# FunctionGen.net
KiCad netlist of a schematic drawn in EAGLE
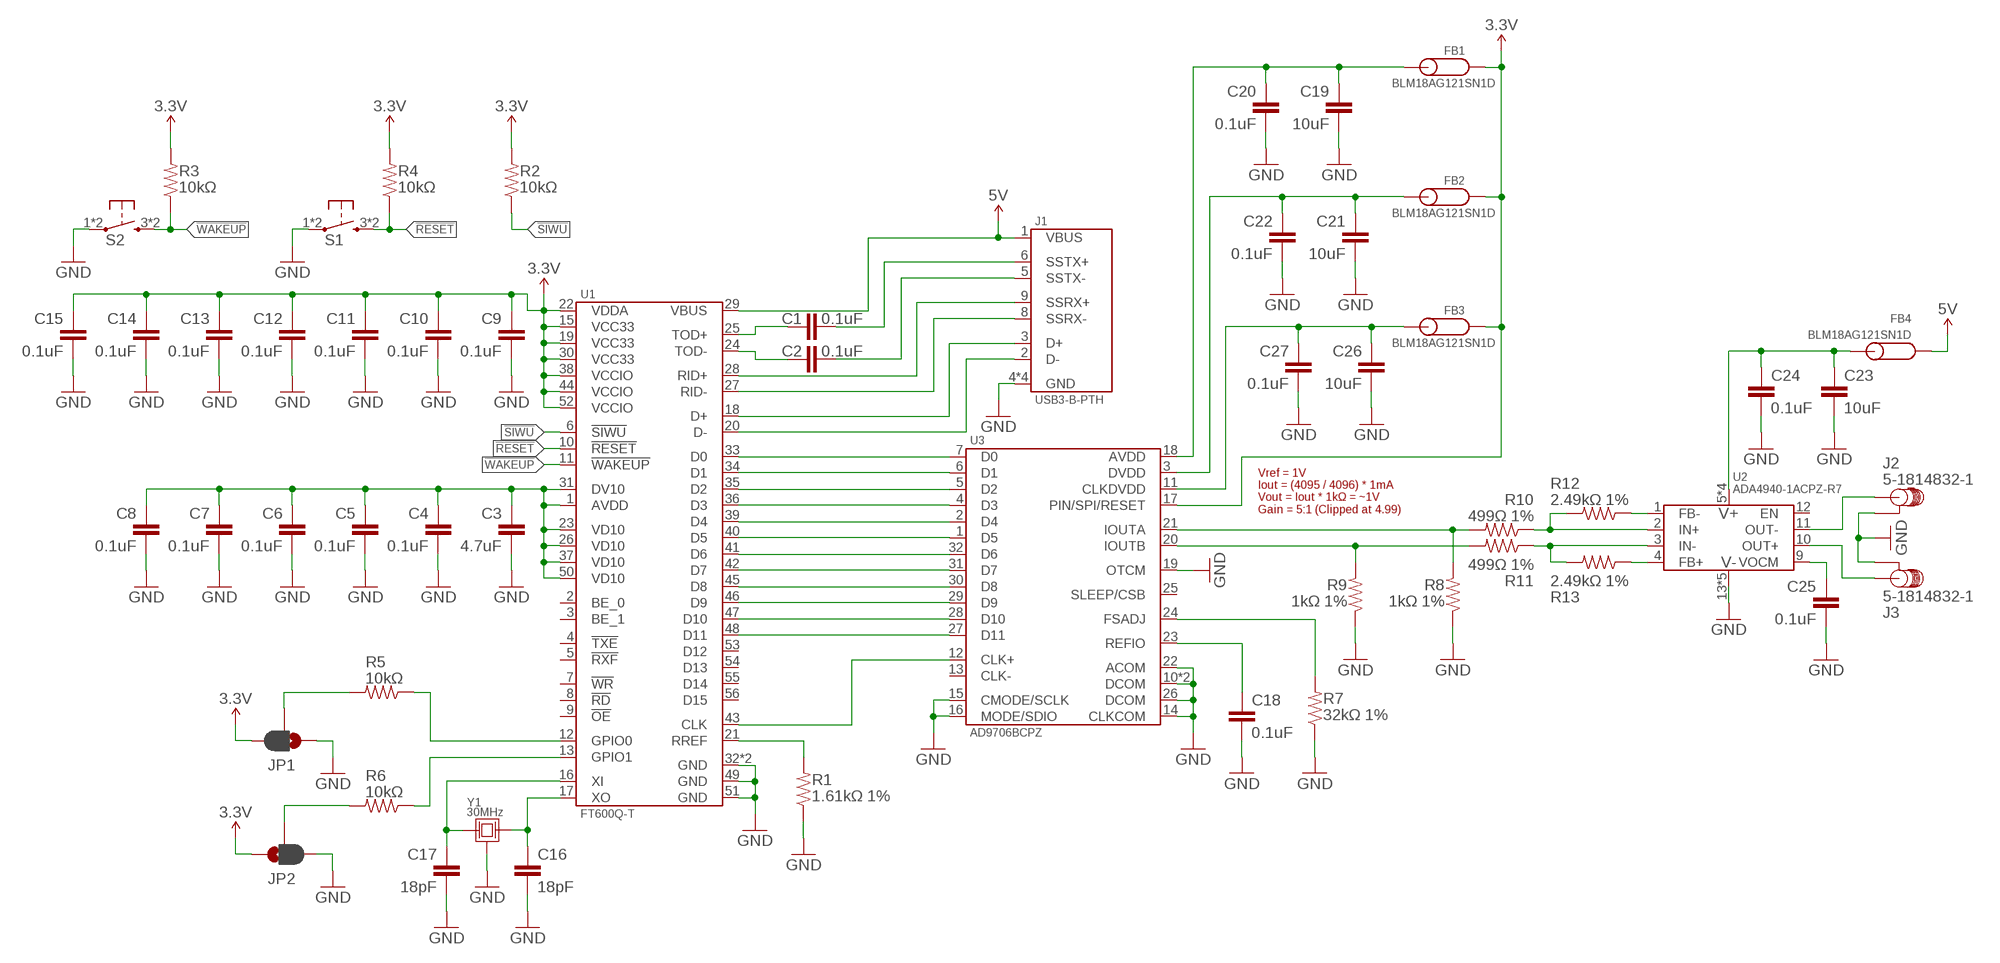
[diagram p0: schematic, sheet 1]

(export (version "E")
  (design (tool "Eeschema 10.0.6"))
  (components
    (comp (ref "C1")
      (value "0.1uF")
      (footprint "eagle-import:0603-CAP")
      (libsource (lib "eagle-import") (part "CAP-0603"))
    )
    (comp (ref "C2")
      (value "0.1uF")
      (footprint "eagle-import:0603-CAP")
      (libsource (lib "eagle-import") (part "CAP-0603"))
    )
    (comp (ref "C3")
      (value "4.7uF")
      (footprint "eagle-import:0603-CAP")
      (libsource (lib "eagle-import") (part "CAP-0603"))
    )
    (comp (ref "C4")
      (value "0.1uF")
      (footprint "eagle-import:0603-CAP")
      (libsource (lib "eagle-import") (part "CAP-0603"))
    )
    (comp (ref "C5")
      (value "0.1uF")
      (footprint "eagle-import:0603-CAP")
      (libsource (lib "eagle-import") (part "CAP-0603"))
    )
    (comp (ref "C6")
      (value "0.1uF")
      (footprint "eagle-import:0603-CAP")
      (libsource (lib "eagle-import") (part "CAP-0603"))
    )
    (comp (ref "C7")
      (value "0.1uF")
      (footprint "eagle-import:0603-CAP")
      (libsource (lib "eagle-import") (part "CAP-0603"))
    )
    (comp (ref "C8")
      (value "0.1uF")
      (footprint "eagle-import:0603-CAP")
      (libsource (lib "eagle-import") (part "CAP-0603"))
    )
    (comp (ref "C9")
      (value "0.1uF")
      (footprint "eagle-import:0603-CAP")
      (libsource (lib "eagle-import") (part "CAP-0603"))
    )
    (comp (ref "C10")
      (value "0.1uF")
      (footprint "eagle-import:0603-CAP")
      (libsource (lib "eagle-import") (part "CAP-0603"))
    )
    (comp (ref "C11")
      (value "0.1uF")
      (footprint "eagle-import:0603-CAP")
      (libsource (lib "eagle-import") (part "CAP-0603"))
    )
    (comp (ref "C12")
      (value "0.1uF")
      (footprint "eagle-import:0603-CAP")
      (libsource (lib "eagle-import") (part "CAP-0603"))
    )
    (comp (ref "C13")
      (value "0.1uF")
      (footprint "eagle-import:0603-CAP")
      (libsource (lib "eagle-import") (part "CAP-0603"))
    )
    (comp (ref "C14")
      (value "0.1uF")
      (footprint "eagle-import:0603-CAP")
      (libsource (lib "eagle-import") (part "CAP-0603"))
    )
    (comp (ref "C15")
      (value "0.1uF")
      (footprint "eagle-import:0603-CAP")
      (libsource (lib "eagle-import") (part "CAP-0603"))
    )
    (comp (ref "C16")
      (value "18pF")
      (footprint "eagle-import:0603-CAP")
      (libsource (lib "eagle-import") (part "CAP-0603"))
    )
    (comp (ref "C17")
      (value "18pF")
      (footprint "eagle-import:0603-CAP")
      (libsource (lib "eagle-import") (part "CAP-0603"))
    )
    (comp (ref "C18")
      (value "0.1uF")
      (footprint "eagle-import:0603-CAP")
      (libsource (lib "eagle-import") (part "CAP-0603"))
    )
    (comp (ref "C19")
      (value "10uF")
      (footprint "eagle-import:0603-CAP")
      (libsource (lib "eagle-import") (part "CAP-0603"))
    )
    (comp (ref "C20")
      (value "0.1uF")
      (footprint "eagle-import:0603-CAP")
      (libsource (lib "eagle-import") (part "CAP-0603"))
    )
    (comp (ref "C21")
      (value "10uF")
      (footprint "eagle-import:0603-CAP")
      (libsource (lib "eagle-import") (part "CAP-0603"))
    )
    (comp (ref "C22")
      (value "0.1uF")
      (footprint "eagle-import:0603-CAP")
      (libsource (lib "eagle-import") (part "CAP-0603"))
    )
    (comp (ref "C23")
      (value "10uF")
      (footprint "eagle-import:0603-CAP")
      (libsource (lib "eagle-import") (part "CAP-0603"))
    )
    (comp (ref "C24")
      (value "0.1uF")
      (footprint "eagle-import:0603-CAP")
      (libsource (lib "eagle-import") (part "CAP-0603"))
    )
    (comp (ref "C25")
      (value "0.1uF")
      (footprint "eagle-import:0603-CAP")
      (libsource (lib "eagle-import") (part "CAP-0603"))
    )
    (comp (ref "C26")
      (value "10uF")
      (footprint "eagle-import:0603-CAP")
      (libsource (lib "eagle-import") (part "CAP-0603"))
    )
    (comp (ref "C27")
      (value "0.1uF")
      (footprint "eagle-import:0603-CAP")
      (libsource (lib "eagle-import") (part "CAP-0603"))
    )
    (comp (ref "FB1")
      (value "BLM18AG121SN1D")
      (footprint "eagle-import:0603-FERRITE")
      (libsource (lib "eagle-import") (part "FERRITE-0603"))
    )
    (comp (ref "FB2")
      (value "BLM18AG121SN1D")
      (footprint "eagle-import:0603-FERRITE")
      (libsource (lib "eagle-import") (part "FERRITE-0603"))
    )
    (comp (ref "FB3")
      (value "BLM18AG121SN1D")
      (footprint "eagle-import:0603-FERRITE")
      (libsource (lib "eagle-import") (part "FERRITE-0603"))
    )
    (comp (ref "FB4")
      (value "BLM18AG121SN1D")
      (footprint "eagle-import:0603-FERRITE")
      (libsource (lib "eagle-import") (part "FERRITE-0603"))
    )
    (comp (ref "J1")
      (value "USB3-B-PTH")
      (footprint "eagle-import:GSB4211311WEU")
      (libsource (lib "eagle-import") (part "USB3-B-PTH"))
    )
    (comp (ref "J2")
      (value "5-1814832-1")
      (footprint "eagle-import:SMA-PTH")
      (libsource (lib "eagle-import") (part "SMA-PTH"))
    )
    (comp (ref "J3")
      (value "5-1814832-1")
      (footprint "eagle-import:SMA-PTH")
      (libsource (lib "eagle-import") (part "SMA-PTH"))
    )
    (comp (ref "JP1")
      (value "JUMPER-PAD-3-2OF3_NC_BY_PASTE")
      (footprint "eagle-import:PAD-JUMPER-3-2OF3_NC_BY_PASTE_YES_SILK_FULL_BOX")
      (libsource (lib "eagle-import") (part "JUMPER-PAD-3-2OF3_NC_BY_PASTE"))
    )
    (comp (ref "JP2")
      (value "JUMPER-PAD-3-2OF3_NC_BY_PASTE")
      (footprint "eagle-import:PAD-JUMPER-3-2OF3_NC_BY_PASTE_YES_SILK_FULL_BOX")
      (libsource (lib "eagle-import") (part "JUMPER-PAD-3-2OF3_NC_BY_PASTE"))
    )
    (comp (ref "R1")
      (value "1.61kΩ 1%")
      (footprint "eagle-import:0603-CAP")
      (libsource (lib "eagle-import") (part "RESISTOR-0603"))
    )
    (comp (ref "R2")
      (value "10kΩ")
      (footprint "eagle-import:0603-CAP")
      (libsource (lib "eagle-import") (part "RESISTOR-0603"))
    )
    (comp (ref "R3")
      (value "10kΩ")
      (footprint "eagle-import:0603-CAP")
      (libsource (lib "eagle-import") (part "RESISTOR-0603"))
    )
    (comp (ref "R4")
      (value "10kΩ")
      (footprint "eagle-import:0603-CAP")
      (libsource (lib "eagle-import") (part "RESISTOR-0603"))
    )
    (comp (ref "R5")
      (value "10kΩ")
      (footprint "eagle-import:0603-CAP")
      (libsource (lib "eagle-import") (part "RESISTOR-0603"))
    )
    (comp (ref "R6")
      (value "10kΩ")
      (footprint "eagle-import:0603-CAP")
      (libsource (lib "eagle-import") (part "RESISTOR-0603"))
    )
    (comp (ref "R7")
      (value "32kΩ 1%")
      (footprint "eagle-import:0603-CAP")
      (libsource (lib "eagle-import") (part "RESISTOR-0603"))
    )
    (comp (ref "R8")
      (value "1kΩ 1%")
      (footprint "eagle-import:0603-CAP")
      (libsource (lib "eagle-import") (part "RESISTOR-0603"))
    )
    (comp (ref "R9")
      (value "1kΩ 1%")
      (footprint "eagle-import:0603-CAP")
      (libsource (lib "eagle-import") (part "RESISTOR-0603"))
    )
    (comp (ref "R10")
      (value "499Ω 1%")
      (footprint "eagle-import:0603-CAP")
      (libsource (lib "eagle-import") (part "RESISTOR-0603"))
    )
    (comp (ref "R11")
      (value "499Ω 1%")
      (footprint "eagle-import:0603-CAP")
      (libsource (lib "eagle-import") (part "RESISTOR-0603"))
    )
    (comp (ref "R12")
      (value "2.49kΩ 1%")
      (footprint "eagle-import:0603-CAP")
      (libsource (lib "eagle-import") (part "RESISTOR-0603"))
    )
    (comp (ref "R13")
      (value "2.49kΩ 1%")
      (footprint "eagle-import:0603-CAP")
      (libsource (lib "eagle-import") (part "RESISTOR-0603"))
    )
    (comp (ref "S1")
      (value "TACTILE-SMD3")
      (footprint "eagle-import:FSM4JSMA")
      (libsource (lib "eagle-import") (part "TACTILE-SMD3"))
    )
    (comp (ref "S2")
      (value "TACTILE-SMD3")
      (footprint "eagle-import:FSM4JSMA")
      (libsource (lib "eagle-import") (part "TACTILE-SMD3"))
    )
    (comp (ref "U1")
      (value "FT600Q-T")
      (footprint "eagle-import:VQFN-56-7MM")
      (libsource (lib "eagle-import") (part "FT600Q-T"))
    )
    (comp (ref "U2")
      (value "ADA4940-1ACPZ-R7")
      (footprint "eagle-import:VQFN-16-3MM")
      (libsource (lib "eagle-import") (part "ADA4940-1ACPZ-R7"))
    )
    (comp (ref "U3")
      (value "AD9706BCPZ")
      (footprint "eagle-import:VQFN-32-5MM")
      (libsource (lib "eagle-import") (part "AD9706BCPZ"))
    )
    (comp (ref "Y1")
      (value "30MHz")
      (footprint "eagle-import:FA-238")
      (libsource (lib "eagle-import") (part "CRYSTAL-3.2X2.5"))
    )
  )
  (nets
    (net (code "1") (name "/~{RESET}") (class "Default")
      (node (ref "R4") (pin "1") (pinfunction "1_1") (pintype "passive"))
      (node (ref "S1") (pin "3") (pinfunction "3_3") (pintype "passive"))
      (node (ref "S1") (pin "4") (pinfunction "3_4") (pintype "passive"))
      (node (ref "U1") (pin "10") (pinfunction "~{RESET}_10") (pintype "bidirectional"))
    )
    (net (code "2") (name "/~{SIWU}") (class "Default")
      (node (ref "R2") (pin "1") (pinfunction "1_1") (pintype "passive"))
      (node (ref "U1") (pin "6") (pinfunction "~{SIWU}_6") (pintype "bidirectional"))
    )
    (net (code "3") (name "/~{WAKEUP}") (class "Default")
      (node (ref "R3") (pin "1") (pinfunction "1_1") (pintype "passive"))
      (node (ref "S2") (pin "3") (pinfunction "3_3") (pintype "passive"))
      (node (ref "S2") (pin "4") (pinfunction "3_4") (pintype "passive"))
      (node (ref "U1") (pin "11") (pinfunction "~{WAKEUP}_11") (pintype "bidirectional"))
    )
    (net (code "4") (name "3.3V") (class "Default")
      (node (ref "C10") (pin "1") (pinfunction "1_1") (pintype "passive"))
      (node (ref "C11") (pin "1") (pinfunction "1_1") (pintype "passive"))
      (node (ref "C12") (pin "1") (pinfunction "1_1") (pintype "passive"))
      (node (ref "C13") (pin "1") (pinfunction "1_1") (pintype "passive"))
      (node (ref "C14") (pin "1") (pinfunction "1_1") (pintype "passive"))
      (node (ref "C15") (pin "1") (pinfunction "1_1") (pintype "passive"))
      (node (ref "C9") (pin "1") (pinfunction "1_1") (pintype "passive"))
      (node (ref "FB1") (pin "P$1") (pinfunction "P$1_P$1") (pintype "bidirectional"))
      (node (ref "FB2") (pin "P$1") (pinfunction "P$1_P$1") (pintype "bidirectional"))
      (node (ref "FB3") (pin "P$1") (pinfunction "P$1_P$1") (pintype "bidirectional"))
      (node (ref "JP1") (pin "3") (pinfunction "3_3") (pintype "passive"))
      (node (ref "JP2") (pin "1") (pinfunction "1_1") (pintype "passive"))
      (node (ref "R2") (pin "2") (pinfunction "2_2") (pintype "passive"))
      (node (ref "R3") (pin "2") (pinfunction "2_2") (pintype "passive"))
      (node (ref "R4") (pin "2") (pinfunction "2_2") (pintype "passive"))
      (node (ref "U1") (pin "15") (pinfunction "VCC33_15") (pintype "bidirectional"))
      (node (ref "U1") (pin "19") (pinfunction "VCC33_19") (pintype "bidirectional"))
      (node (ref "U1") (pin "22") (pinfunction "VDDA_22") (pintype "bidirectional"))
      (node (ref "U1") (pin "30") (pinfunction "VCC33_30") (pintype "bidirectional"))
      (node (ref "U1") (pin "38") (pinfunction "VCCIO_38") (pintype "bidirectional"))
      (node (ref "U1") (pin "44") (pinfunction "VCCIO_44") (pintype "bidirectional"))
      (node (ref "U1") (pin "52") (pinfunction "VCCIO_52") (pintype "bidirectional"))
      (node (ref "U3") (pin "17") (pinfunction "PIN/SPI/RESET_17") (pintype "bidirectional"))
    )
    (net (code "5") (name "5V") (class "Default")
      (node (ref "FB4") (pin "P$1") (pinfunction "P$1_P$1") (pintype "bidirectional"))
      (node (ref "J1") (pin "1") (pinfunction "VBUS_1") (pintype "bidirectional"))
      (node (ref "U1") (pin "29") (pinfunction "VBUS_29") (pintype "bidirectional"))
    )
    (net (code "6") (name "GND") (class "Default")
      (node (ref "C10") (pin "2") (pinfunction "2_2") (pintype "passive"))
      (node (ref "C11") (pin "2") (pinfunction "2_2") (pintype "passive"))
      (node (ref "C12") (pin "2") (pinfunction "2_2") (pintype "passive"))
      (node (ref "C13") (pin "2") (pinfunction "2_2") (pintype "passive"))
      (node (ref "C14") (pin "2") (pinfunction "2_2") (pintype "passive"))
      (node (ref "C15") (pin "2") (pinfunction "2_2") (pintype "passive"))
      (node (ref "C16") (pin "2") (pinfunction "2_2") (pintype "passive"))
      (node (ref "C17") (pin "2") (pinfunction "2_2") (pintype "passive"))
      (node (ref "C18") (pin "2") (pinfunction "2_2") (pintype "passive"))
      (node (ref "C19") (pin "2") (pinfunction "2_2") (pintype "passive"))
      (node (ref "C20") (pin "2") (pinfunction "2_2") (pintype "passive"))
      (node (ref "C21") (pin "2") (pinfunction "2_2") (pintype "passive"))
      (node (ref "C22") (pin "2") (pinfunction "2_2") (pintype "passive"))
      (node (ref "C23") (pin "2") (pinfunction "2_2") (pintype "passive"))
      (node (ref "C24") (pin "2") (pinfunction "2_2") (pintype "passive"))
      (node (ref "C25") (pin "2") (pinfunction "2_2") (pintype "passive"))
      (node (ref "C26") (pin "2") (pinfunction "2_2") (pintype "passive"))
      (node (ref "C27") (pin "2") (pinfunction "2_2") (pintype "passive"))
      (node (ref "C3") (pin "2") (pinfunction "2_2") (pintype "passive"))
      (node (ref "C4") (pin "2") (pinfunction "2_2") (pintype "passive"))
      (node (ref "C5") (pin "2") (pinfunction "2_2") (pintype "passive"))
      (node (ref "C6") (pin "2") (pinfunction "2_2") (pintype "passive"))
      (node (ref "C7") (pin "2") (pinfunction "2_2") (pintype "passive"))
      (node (ref "C8") (pin "2") (pinfunction "2_2") (pintype "passive"))
      (node (ref "C9") (pin "2") (pinfunction "2_2") (pintype "passive"))
      (node (ref "J1") (pin "4") (pinfunction "GND_4") (pintype "bidirectional"))
      (node (ref "J1") (pin "7") (pinfunction "GND_7") (pintype "bidirectional"))
      (node (ref "J1") (pin "P$10") (pinfunction "GND_P$10") (pintype "bidirectional"))
      (node (ref "J1") (pin "P$11") (pinfunction "GND_P$11") (pintype "bidirectional"))
      (node (ref "J2") (pin "P$1") (pinfunction "GND_P$1") (pintype "bidirectional"))
      (node (ref "J2") (pin "P$2") (pinfunction "GND_P$2") (pintype "bidirectional"))
      (node (ref "J2") (pin "P$3") (pinfunction "GND_P$3") (pintype "bidirectional"))
      (node (ref "J2") (pin "P$4") (pinfunction "GND_P$4") (pintype "bidirectional"))
      (node (ref "J3") (pin "P$1") (pinfunction "GND_P$1") (pintype "bidirectional"))
      (node (ref "J3") (pin "P$2") (pinfunction "GND_P$2") (pintype "bidirectional"))
      (node (ref "J3") (pin "P$3") (pinfunction "GND_P$3") (pintype "bidirectional"))
      (node (ref "J3") (pin "P$4") (pinfunction "GND_P$4") (pintype "bidirectional"))
      (node (ref "JP1") (pin "1") (pinfunction "1_1") (pintype "passive"))
      (node (ref "JP2") (pin "3") (pinfunction "3_3") (pintype "passive"))
      (node (ref "R1") (pin "1") (pinfunction "1_1") (pintype "passive"))
      (node (ref "R7") (pin "1") (pinfunction "1_1") (pintype "passive"))
      (node (ref "R8") (pin "1") (pinfunction "1_1") (pintype "passive"))
      (node (ref "R9") (pin "1") (pinfunction "1_1") (pintype "passive"))
      (node (ref "S1") (pin "1") (pinfunction "1_1") (pintype "passive"))
      (node (ref "S1") (pin "2") (pinfunction "1_2") (pintype "passive"))
      (node (ref "S2") (pin "1") (pinfunction "1_1") (pintype "passive"))
      (node (ref "S2") (pin "2") (pinfunction "1_2") (pintype "passive"))
      (node (ref "U1") (pin "32") (pinfunction "GND_32") (pintype "bidirectional"))
      (node (ref "U1") (pin "49") (pinfunction "GND_49") (pintype "bidirectional"))
      (node (ref "U1") (pin "51") (pinfunction "GND_51") (pintype "bidirectional"))
      (node (ref "U1") (pin "PAD") (pinfunction "GND_PAD") (pintype "bidirectional"))
      (node (ref "U2") (pin "13") (pinfunction "VS-_13") (pintype "bidirectional"))
      (node (ref "U2") (pin "14") (pinfunction "VS-_14") (pintype "bidirectional"))
      (node (ref "U2") (pin "15") (pinfunction "VS-_15") (pintype "bidirectional"))
      (node (ref "U2") (pin "16") (pinfunction "VS-_16") (pintype "bidirectional"))
      (node (ref "U2") (pin "PAD") (pinfunction "VS-_PAD") (pintype "bidirectional"))
      (node (ref "U3") (pin "10") (pinfunction "DCOM_10") (pintype "bidirectional"))
      (node (ref "U3") (pin "14") (pinfunction "CLKCOM_14") (pintype "bidirectional"))
      (node (ref "U3") (pin "15") (pinfunction "CMODE/SCLK_15") (pintype "bidirectional"))
      (node (ref "U3") (pin "16") (pinfunction "MODE/SDIO_16") (pintype "bidirectional"))
      (node (ref "U3") (pin "19") (pinfunction "OTCM_19") (pintype "bidirectional"))
      (node (ref "U3") (pin "22") (pinfunction "ACOM_22") (pintype "bidirectional"))
      (node (ref "U3") (pin "26") (pinfunction "DCOM_26") (pintype "bidirectional"))
      (node (ref "U3") (pin "PAD") (pinfunction "DCOM_PAD") (pintype "bidirectional"))
      (node (ref "Y1") (pin "2") (pinfunction "GND_2") (pintype "bidirectional"))
      (node (ref "Y1") (pin "4") (pinfunction "GND_4") (pintype "bidirectional"))
    )
    (net (code "7") (name "Net-(C23-Pad1)") (class "Default")
      (node (ref "C23") (pin "1") (pinfunction "1_1") (pintype "passive"))
      (node (ref "C24") (pin "1") (pinfunction "1_1") (pintype "passive"))
      (node (ref "FB4") (pin "P$2") (pinfunction "P$2_P$2") (pintype "bidirectional"))
      (node (ref "U2") (pin "5") (pinfunction "VS+_5") (pintype "bidirectional"))
      (node (ref "U2") (pin "6") (pinfunction "VS+_6") (pintype "bidirectional"))
      (node (ref "U2") (pin "7") (pinfunction "VS+_7") (pintype "bidirectional"))
      (node (ref "U2") (pin "8") (pinfunction "VS+_8") (pintype "bidirectional"))
    )
    (net (code "8") (name "Net-(J1-D+)") (class "Default")
      (node (ref "J1") (pin "3") (pinfunction "D+_3") (pintype "bidirectional"))
      (node (ref "U1") (pin "18") (pinfunction "D+_18") (pintype "bidirectional"))
    )
    (net (code "9") (name "Net-(J1-D-)") (class "Default")
      (node (ref "J1") (pin "2") (pinfunction "D-_2") (pintype "bidirectional"))
      (node (ref "U1") (pin "20") (pinfunction "D-_20") (pintype "bidirectional"))
    )
    (net (code "10") (name "Net-(J1-SSRX+)") (class "Default")
      (node (ref "J1") (pin "9") (pinfunction "SSRX+_9") (pintype "bidirectional"))
      (node (ref "U1") (pin "28") (pinfunction "RID+_28") (pintype "bidirectional"))
    )
    (net (code "11") (name "Net-(J1-SSRX-)") (class "Default")
      (node (ref "J1") (pin "8") (pinfunction "SSRX-_8") (pintype "bidirectional"))
      (node (ref "U1") (pin "27") (pinfunction "RID-_27") (pintype "bidirectional"))
    )
    (net (code "12") (name "Net-(J1-SSTX+)") (class "Default")
      (node (ref "C1") (pin "2") (pinfunction "2_2") (pintype "passive"))
      (node (ref "J1") (pin "6") (pinfunction "SSTX+_6") (pintype "bidirectional"))
    )
    (net (code "13") (name "Net-(J1-SSTX-)") (class "Default")
      (node (ref "C2") (pin "2") (pinfunction "2_2") (pintype "passive"))
      (node (ref "J1") (pin "5") (pinfunction "SSTX-_5") (pintype "bidirectional"))
    )
    (net (code "14") (name "Net-(JP1-Pad2)") (class "Default")
      (node (ref "JP1") (pin "2") (pinfunction "2_2") (pintype "passive"))
      (node (ref "R5") (pin "2") (pinfunction "2_2") (pintype "passive"))
    )
    (net (code "15") (name "Net-(JP2-Pad2)") (class "Default")
      (node (ref "JP2") (pin "2") (pinfunction "2_2") (pintype "passive"))
      (node (ref "R6") (pin "2") (pinfunction "2_2") (pintype "passive"))
    )
    (net (code "16") (name "Net-(U1-AVDD)") (class "Default")
      (node (ref "C3") (pin "1") (pinfunction "1_1") (pintype "passive"))
      (node (ref "C4") (pin "1") (pinfunction "1_1") (pintype "passive"))
      (node (ref "C5") (pin "1") (pinfunction "1_1") (pintype "passive"))
      (node (ref "C6") (pin "1") (pinfunction "1_1") (pintype "passive"))
      (node (ref "C7") (pin "1") (pinfunction "1_1") (pintype "passive"))
      (node (ref "C8") (pin "1") (pinfunction "1_1") (pintype "passive"))
      (node (ref "U1") (pin "1") (pinfunction "AVDD_1") (pintype "bidirectional"))
      (node (ref "U1") (pin "23") (pinfunction "VD10_23") (pintype "bidirectional"))
      (node (ref "U1") (pin "26") (pinfunction "VD10_26") (pintype "bidirectional"))
      (node (ref "U1") (pin "31") (pinfunction "DV10_31") (pintype "bidirectional"))
      (node (ref "U1") (pin "37") (pinfunction "VD10_37") (pintype "bidirectional"))
      (node (ref "U1") (pin "50") (pinfunction "VD10_50") (pintype "bidirectional"))
    )
    (net (code "17") (name "Net-(U1-CLK)") (class "Default")
      (node (ref "U1") (pin "43") (pinfunction "CLK_43") (pintype "bidirectional"))
      (node (ref "U3") (pin "12") (pinfunction "CLK+_12") (pintype "bidirectional"))
    )
    (net (code "18") (name "Net-(U1-D0)") (class "Default")
      (node (ref "U1") (pin "33") (pinfunction "D0_33") (pintype "bidirectional"))
      (node (ref "U3") (pin "7") (pinfunction "D0_7") (pintype "bidirectional"))
    )
    (net (code "19") (name "Net-(U1-D1)") (class "Default")
      (node (ref "U1") (pin "34") (pinfunction "D1_34") (pintype "bidirectional"))
      (node (ref "U3") (pin "6") (pinfunction "D1_6") (pintype "bidirectional"))
    )
    (net (code "20") (name "Net-(U1-D2)") (class "Default")
      (node (ref "U1") (pin "35") (pinfunction "D2_35") (pintype "bidirectional"))
      (node (ref "U3") (pin "5") (pinfunction "D2_5") (pintype "bidirectional"))
    )
    (net (code "21") (name "Net-(U1-D3)") (class "Default")
      (node (ref "U1") (pin "36") (pinfunction "D3_36") (pintype "bidirectional"))
      (node (ref "U3") (pin "4") (pinfunction "D3_4") (pintype "bidirectional"))
    )
    (net (code "22") (name "Net-(U1-D4)") (class "Default")
      (node (ref "U1") (pin "39") (pinfunction "D4_39") (pintype "bidirectional"))
      (node (ref "U3") (pin "2") (pinfunction "D4_2") (pintype "bidirectional"))
    )
    (net (code "23") (name "Net-(U1-D5)") (class "Default")
      (node (ref "U1") (pin "40") (pinfunction "D5_40") (pintype "bidirectional"))
      (node (ref "U3") (pin "1") (pinfunction "D5_1") (pintype "bidirectional"))
    )
    (net (code "24") (name "Net-(U1-D6)") (class "Default")
      (node (ref "U1") (pin "41") (pinfunction "D6_41") (pintype "bidirectional"))
      (node (ref "U3") (pin "32") (pinfunction "D6_32") (pintype "bidirectional"))
    )
    (net (code "25") (name "Net-(U1-D7)") (class "Default")
      (node (ref "U1") (pin "42") (pinfunction "D7_42") (pintype "bidirectional"))
      (node (ref "U3") (pin "31") (pinfunction "D7_31") (pintype "bidirectional"))
    )
    (net (code "26") (name "Net-(U1-D8)") (class "Default")
      (node (ref "U1") (pin "45") (pinfunction "D8_45") (pintype "bidirectional"))
      (node (ref "U3") (pin "30") (pinfunction "D8_30") (pintype "bidirectional"))
    )
    (net (code "27") (name "Net-(U1-D9)") (class "Default")
      (node (ref "U1") (pin "46") (pinfunction "D9_46") (pintype "bidirectional"))
      (node (ref "U3") (pin "29") (pinfunction "D9_29") (pintype "bidirectional"))
    )
    (net (code "28") (name "Net-(U1-D10)") (class "Default")
      (node (ref "U1") (pin "47") (pinfunction "D10_47") (pintype "bidirectional"))
      (node (ref "U3") (pin "28") (pinfunction "D10_28") (pintype "bidirectional"))
    )
    (net (code "29") (name "Net-(U1-D11)") (class "Default")
      (node (ref "U1") (pin "48") (pinfunction "D11_48") (pintype "bidirectional"))
      (node (ref "U3") (pin "27") (pinfunction "D11_27") (pintype "bidirectional"))
    )
    (net (code "30") (name "Net-(U1-GPIO0)") (class "Default")
      (node (ref "R5") (pin "1") (pinfunction "1_1") (pintype "passive"))
      (node (ref "U1") (pin "12") (pinfunction "GPIO0_12") (pintype "bidirectional"))
    )
    (net (code "31") (name "Net-(U1-GPIO1)") (class "Default")
      (node (ref "R6") (pin "1") (pinfunction "1_1") (pintype "passive"))
      (node (ref "U1") (pin "13") (pinfunction "GPIO1_13") (pintype "bidirectional"))
    )
    (net (code "32") (name "Net-(U1-RREF)") (class "Default")
      (node (ref "R1") (pin "2") (pinfunction "2_2") (pintype "passive"))
      (node (ref "U1") (pin "21") (pinfunction "RREF_21") (pintype "bidirectional"))
    )
    (net (code "33") (name "Net-(U1-TOD+)") (class "Default")
      (node (ref "C1") (pin "1") (pinfunction "1_1") (pintype "passive"))
      (node (ref "U1") (pin "25") (pinfunction "TOD+_25") (pintype "bidirectional"))
    )
    (net (code "34") (name "Net-(U1-TOD-)") (class "Default")
      (node (ref "C2") (pin "1") (pinfunction "1_1") (pintype "passive"))
      (node (ref "U1") (pin "24") (pinfunction "TOD-_24") (pintype "bidirectional"))
    )
    (net (code "35") (name "Net-(U1-XI)") (class "Default")
      (node (ref "C17") (pin "1") (pinfunction "1_1") (pintype "passive"))
      (node (ref "U1") (pin "16") (pinfunction "XI_16") (pintype "bidirectional"))
      (node (ref "Y1") (pin "1") (pinfunction "1_1") (pintype "bidirectional"))
    )
    (net (code "36") (name "Net-(U1-XO)") (class "Default")
      (node (ref "C16") (pin "1") (pinfunction "1_1") (pintype "passive"))
      (node (ref "U1") (pin "17") (pinfunction "XO_17") (pintype "bidirectional"))
      (node (ref "Y1") (pin "3") (pinfunction "2_3") (pintype "bidirectional"))
    )
    (net (code "37") (name "Net-(U2-FB+)") (class "Default")
      (node (ref "R13") (pin "1") (pinfunction "1_1") (pintype "passive"))
      (node (ref "U2") (pin "4") (pinfunction "FB+_4") (pintype "bidirectional"))
    )
    (net (code "38") (name "Net-(U2-FB-)") (class "Default")
      (node (ref "R12") (pin "1") (pinfunction "1_1") (pintype "passive"))
      (node (ref "U2") (pin "1") (pinfunction "FB-_1") (pintype "bidirectional"))
    )
    (net (code "39") (name "Net-(U2-IN+)") (class "Default")
      (node (ref "R10") (pin "1") (pinfunction "1_1") (pintype "passive"))
      (node (ref "R12") (pin "2") (pinfunction "2_2") (pintype "passive"))
      (node (ref "U2") (pin "2") (pinfunction "IN+_2") (pintype "bidirectional"))
    )
    (net (code "40") (name "Net-(U2-IN-)") (class "Default")
      (node (ref "R11") (pin "1") (pinfunction "1_1") (pintype "passive"))
      (node (ref "R13") (pin "2") (pinfunction "2_2") (pintype "passive"))
      (node (ref "U2") (pin "3") (pinfunction "IN-_3") (pintype "bidirectional"))
    )
    (net (code "41") (name "Net-(U2-OUT+)") (class "Default")
      (node (ref "J3") (pin "SIGNAL") (pinfunction "SIGNAL_SIGNAL") (pintype "bidirectional"))
      (node (ref "U2") (pin "10") (pinfunction "OUT+_10") (pintype "bidirectional"))
    )
    (net (code "42") (name "Net-(U2-OUT-)") (class "Default")
      (node (ref "J2") (pin "SIGNAL") (pinfunction "SIGNAL_SIGNAL") (pintype "bidirectional"))
      (node (ref "U2") (pin "11") (pinfunction "OUT-_11") (pintype "bidirectional"))
    )
    (net (code "43") (name "Net-(U2-VOCM)") (class "Default")
      (node (ref "C25") (pin "1") (pinfunction "1_1") (pintype "passive"))
      (node (ref "U2") (pin "9") (pinfunction "VOCM_9") (pintype "bidirectional"))
    )
    (net (code "44") (name "Net-(U3-AVDD)") (class "Default")
      (node (ref "C19") (pin "1") (pinfunction "1_1") (pintype "passive"))
      (node (ref "C20") (pin "1") (pinfunction "1_1") (pintype "passive"))
      (node (ref "FB1") (pin "P$2") (pinfunction "P$2_P$2") (pintype "bidirectional"))
      (node (ref "U3") (pin "18") (pinfunction "AVDD_18") (pintype "bidirectional"))
    )
    (net (code "45") (name "Net-(U3-CLKDVDD)") (class "Default")
      (node (ref "C26") (pin "1") (pinfunction "1_1") (pintype "passive"))
      (node (ref "C27") (pin "1") (pinfunction "1_1") (pintype "passive"))
      (node (ref "FB3") (pin "P$2") (pinfunction "P$2_P$2") (pintype "bidirectional"))
      (node (ref "U3") (pin "11") (pinfunction "CLKDVDD_11") (pintype "bidirectional"))
    )
    (net (code "46") (name "Net-(U3-DVDD)") (class "Default")
      (node (ref "C21") (pin "1") (pinfunction "1_1") (pintype "passive"))
      (node (ref "C22") (pin "1") (pinfunction "1_1") (pintype "passive"))
      (node (ref "FB2") (pin "P$2") (pinfunction "P$2_P$2") (pintype "bidirectional"))
      (node (ref "U3") (pin "3") (pinfunction "DVDD_3") (pintype "bidirectional"))
    )
    (net (code "47") (name "Net-(U3-FSADJ)") (class "Default")
      (node (ref "R7") (pin "2") (pinfunction "2_2") (pintype "passive"))
      (node (ref "U3") (pin "24") (pinfunction "FSADJ_24") (pintype "bidirectional"))
    )
    (net (code "48") (name "Net-(U3-IOUTA)") (class "Default")
      (node (ref "R10") (pin "2") (pinfunction "2_2") (pintype "passive"))
      (node (ref "R8") (pin "2") (pinfunction "2_2") (pintype "passive"))
      (node (ref "U3") (pin "21") (pinfunction "IOUTA_21") (pintype "bidirectional"))
    )
    (net (code "49") (name "Net-(U3-IOUTB)") (class "Default")
      (node (ref "R11") (pin "2") (pinfunction "2_2") (pintype "passive"))
      (node (ref "R9") (pin "2") (pinfunction "2_2") (pintype "passive"))
      (node (ref "U3") (pin "20") (pinfunction "IOUTB_20") (pintype "bidirectional"))
    )
    (net (code "50") (name "Net-(U3-REFIO)") (class "Default")
      (node (ref "C18") (pin "1") (pinfunction "1_1") (pintype "passive"))
      (node (ref "U3") (pin "23") (pinfunction "REFIO_23") (pintype "bidirectional"))
    )
    (net (code "51") (name "unconnected-(U1-BE_0-Pad2)") (class "Default")
      (node (ref "U1") (pin "2") (pinfunction "BE_0_2") (pintype "bidirectional"))
    )
    (net (code "52") (name "unconnected-(U1-BE_1-Pad3)") (class "Default")
      (node (ref "U1") (pin "3") (pinfunction "BE_1_3") (pintype "bidirectional"))
    )
    (net (code "53") (name "unconnected-(U1-D12-Pad53)") (class "Default")
      (node (ref "U1") (pin "53") (pinfunction "D12_53") (pintype "bidirectional"))
    )
    (net (code "54") (name "unconnected-(U1-D13-Pad54)") (class "Default")
      (node (ref "U1") (pin "54") (pinfunction "D13_54") (pintype "bidirectional"))
    )
    (net (code "55") (name "unconnected-(U1-D14-Pad55)") (class "Default")
      (node (ref "U1") (pin "55") (pinfunction "D14_55") (pintype "bidirectional"))
    )
    (net (code "56") (name "unconnected-(U1-D15-Pad56)") (class "Default")
      (node (ref "U1") (pin "56") (pinfunction "D15_56") (pintype "bidirectional"))
    )
    (net (code "57") (name "unconnected-(U1-~{OE}-Pad9)") (class "Default")
      (node (ref "U1") (pin "9") (pinfunction "~{OE}_9") (pintype "bidirectional"))
    )
    (net (code "58") (name "unconnected-(U1-~{RD}-Pad8)") (class "Default")
      (node (ref "U1") (pin "8") (pinfunction "~{RD}_8") (pintype "bidirectional"))
    )
    (net (code "59") (name "unconnected-(U1-~{RXF}-Pad5)") (class "Default")
      (node (ref "U1") (pin "5") (pinfunction "~{RXF}_5") (pintype "bidirectional"))
    )
    (net (code "60") (name "unconnected-(U1-~{TXE}-Pad4)") (class "Default")
      (node (ref "U1") (pin "4") (pinfunction "~{TXE}_4") (pintype "bidirectional"))
    )
    (net (code "61") (name "unconnected-(U1-~{WR}-Pad7)") (class "Default")
      (node (ref "U1") (pin "7") (pinfunction "~{WR}_7") (pintype "bidirectional"))
    )
    (net (code "62") (name "unconnected-(U2-EN-Pad12)") (class "Default")
      (node (ref "U2") (pin "12") (pinfunction "EN_12") (pintype "bidirectional"))
    )
    (net (code "63") (name "unconnected-(U3-CLK--Pad13)") (class "Default")
      (node (ref "U3") (pin "13") (pinfunction "CLK-_13") (pintype "bidirectional"))
    )
    (net (code "64") (name "unconnected-(U3-SLEEP{slash}CSB-Pad25)") (class "Default")
      (node (ref "U3") (pin "25") (pinfunction "SLEEP/CSB_25") (pintype "bidirectional"))
    )
  )
)
